# LTC3109.net
KiCad netlist of a schematic drawn in EAGLE
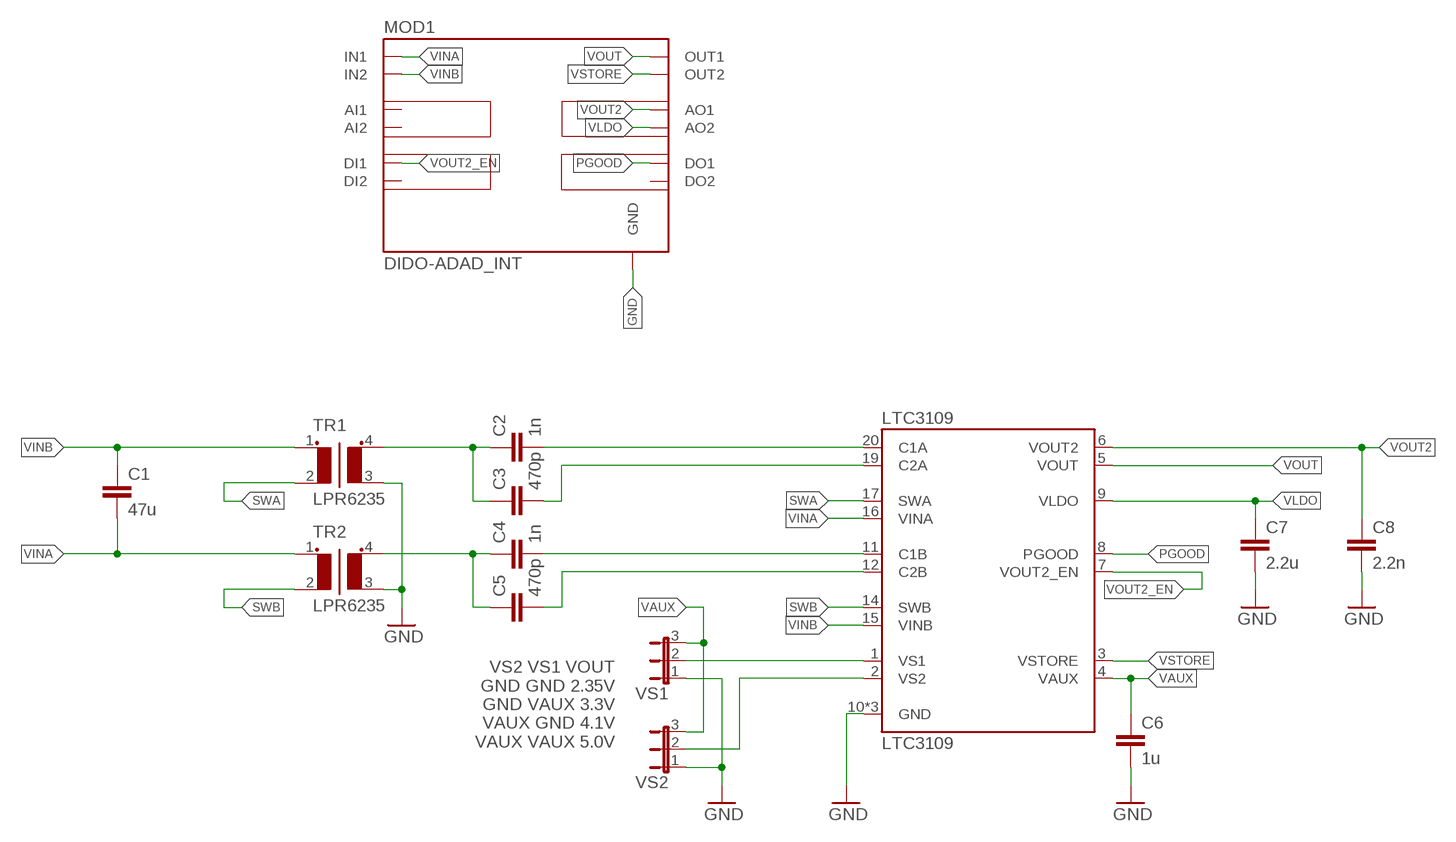
[diagram p0: schematic, sheet 1]

(export (version "E")
  (design (tool "Eeschema 10.0.6"))
  (components
    (comp (ref "C1")
      (value "47u")
      (footprint "eagle-import:C0805")
      (libsource (lib "eagle-import") (part "C-EUC0805"))
    )
    (comp (ref "C2")
      (value "1n")
      (footprint "eagle-import:C0805")
      (libsource (lib "eagle-import") (part "C-EUC0805"))
    )
    (comp (ref "C3")
      (value "470p")
      (footprint "eagle-import:C0805")
      (libsource (lib "eagle-import") (part "C-EUC0805"))
    )
    (comp (ref "C4")
      (value "1n")
      (footprint "eagle-import:C0805")
      (libsource (lib "eagle-import") (part "C-EUC0805"))
    )
    (comp (ref "C5")
      (value "470p")
      (footprint "eagle-import:C0805")
      (libsource (lib "eagle-import") (part "C-EUC0805"))
    )
    (comp (ref "C6")
      (value "1u")
      (footprint "eagle-import:C0805")
      (libsource (lib "eagle-import") (part "C-EUC0805"))
    )
    (comp (ref "C7")
      (value "2.2u")
      (footprint "eagle-import:C0805")
      (libsource (lib "eagle-import") (part "C-EUC0805"))
    )
    (comp (ref "C8")
      (value "2.2n")
      (footprint "eagle-import:C0805")
      (libsource (lib "eagle-import") (part "C-EUC0805"))
    )
    (comp (ref "LTC3109")
      (value "LTC3109")
      (footprint "eagle-import:SSOP20_NARROW")
      (libsource (lib "eagle-import") (part "LTC3109"))
    )
    (comp (ref "MOD1")
      (value "DIDO-ADAD_INT")
      (footprint "eagle-import:DIDO-ADAD")
      (libsource (lib "eagle-import") (part "DIDO-ADAD_INT"))
    )
    (comp (ref "TR1")
      (value "LPR6235")
      (footprint "eagle-import:LPR6235")
      (libsource (lib "eagle-import") (part "LPR6235"))
    )
    (comp (ref "TR2")
      (value "LPR6235")
      (footprint "eagle-import:LPR6235")
      (libsource (lib "eagle-import") (part "LPR6235"))
    )
    (comp (ref "VS1")
      (value "JP2E")
      (footprint "eagle-import:JP2")
      (libsource (lib "eagle-import") (part "JP2E"))
    )
    (comp (ref "VS2")
      (value "JP2E")
      (footprint "eagle-import:JP2")
      (libsource (lib "eagle-import") (part "JP2E"))
    )
  )
  (nets
    (net (code "1") (name "GND") (class "Default")
      (node (ref "C6") (pin "2") (pinfunction "2_2") (pintype "passive"))
      (node (ref "C7") (pin "2") (pinfunction "2_2") (pintype "passive"))
      (node (ref "C8") (pin "2") (pinfunction "2_2") (pintype "passive"))
      (node (ref "LTC3109") (pin "10") (pinfunction "GND_10") (pintype "power_in"))
      (node (ref "LTC3109") (pin "13") (pinfunction "GND_13") (pintype "power_in"))
      (node (ref "LTC3109") (pin "18") (pinfunction "GND_18") (pintype "power_in"))
      (node (ref "MOD1") (pin "GND1") (pinfunction "GND_GND1") (pintype "power_in"))
      (node (ref "MOD1") (pin "GND2") (pinfunction "GND_GND2") (pintype "power_in"))
      (node (ref "MOD1") (pin "GND3") (pinfunction "GND_GND3") (pintype "power_in"))
      (node (ref "MOD1") (pin "GND4") (pinfunction "GND_GND4") (pintype "power_in"))
      (node (ref "TR1") (pin "3") (pinfunction "S2_3") (pintype "passive"))
      (node (ref "TR2") (pin "3") (pinfunction "S2_3") (pintype "passive"))
      (node (ref "VS1") (pin "1") (pinfunction "1_1") (pintype "passive"))
      (node (ref "VS2") (pin "1") (pinfunction "1_1") (pintype "passive"))
    )
    (net (code "2") (name "Net-(LTC3109-C1A)") (class "Default")
      (node (ref "C2") (pin "2") (pinfunction "2_2") (pintype "passive"))
      (node (ref "LTC3109") (pin "20") (pinfunction "C1A_20") (pintype "input"))
    )
    (net (code "3") (name "Net-(LTC3109-C1B)") (class "Default")
      (node (ref "C4") (pin "2") (pinfunction "2_2") (pintype "passive"))
      (node (ref "LTC3109") (pin "11") (pinfunction "C1B_11") (pintype "input"))
    )
    (net (code "4") (name "Net-(LTC3109-C2A)") (class "Default")
      (node (ref "C3") (pin "2") (pinfunction "2_2") (pintype "passive"))
      (node (ref "LTC3109") (pin "19") (pinfunction "C2A_19") (pintype "input"))
    )
    (net (code "5") (name "Net-(LTC3109-C2B)") (class "Default")
      (node (ref "C5") (pin "2") (pinfunction "2_2") (pintype "passive"))
      (node (ref "LTC3109") (pin "12") (pinfunction "C2B_12") (pintype "input"))
    )
    (net (code "6") (name "Net-(LTC3109-VS1)") (class "Default")
      (node (ref "LTC3109") (pin "1") (pinfunction "VS1_1") (pintype "bidirectional"))
      (node (ref "VS1") (pin "2") (pinfunction "2_2") (pintype "passive"))
    )
    (net (code "7") (name "Net-(LTC3109-VS2)") (class "Default")
      (node (ref "LTC3109") (pin "2") (pinfunction "VS2_2") (pintype "bidirectional"))
      (node (ref "VS2") (pin "2") (pinfunction "2_2") (pintype "passive"))
    )
    (net (code "8") (name "Net-(TR1-S1)") (class "Default")
      (node (ref "C2") (pin "1") (pinfunction "1_1") (pintype "passive"))
      (node (ref "C3") (pin "1") (pinfunction "1_1") (pintype "passive"))
      (node (ref "TR1") (pin "4") (pinfunction "S1_4") (pintype "passive"))
    )
    (net (code "9") (name "Net-(TR2-S1)") (class "Default")
      (node (ref "C4") (pin "1") (pinfunction "1_1") (pintype "passive"))
      (node (ref "C5") (pin "1") (pinfunction "1_1") (pintype "passive"))
      (node (ref "TR2") (pin "4") (pinfunction "S1_4") (pintype "passive"))
    )
    (net (code "10") (name "PGOOD") (class "Default")
      (node (ref "LTC3109") (pin "8") (pinfunction "PGOOD_8") (pintype "output"))
      (node (ref "MOD1") (pin "DO1") (pinfunction "DO1_DO1") (pintype "input"))
    )
    (net (code "11") (name "SWA") (class "Default")
      (node (ref "LTC3109") (pin "17") (pinfunction "SWA_17") (pintype "bidirectional"))
      (node (ref "TR1") (pin "2") (pinfunction "P2_2") (pintype "passive"))
    )
    (net (code "12") (name "SWB") (class "Default")
      (node (ref "LTC3109") (pin "14") (pinfunction "SWB_14") (pintype "bidirectional"))
      (node (ref "TR2") (pin "2") (pinfunction "P2_2") (pintype "passive"))
    )
    (net (code "13") (name "VAUX") (class "Default")
      (node (ref "C6") (pin "1") (pinfunction "1_1") (pintype "passive"))
      (node (ref "LTC3109") (pin "4") (pinfunction "VAUX_4") (pintype "output"))
      (node (ref "VS1") (pin "3") (pinfunction "3_3") (pintype "passive"))
      (node (ref "VS2") (pin "3") (pinfunction "3_3") (pintype "passive"))
    )
    (net (code "14") (name "VINA") (class "Default")
      (node (ref "C1") (pin "2") (pinfunction "2_2") (pintype "passive"))
      (node (ref "LTC3109") (pin "16") (pinfunction "VINA_16") (pintype "bidirectional"))
      (node (ref "MOD1") (pin "IN1_1") (pinfunction "IN1_IN1_1") (pintype "output"))
      (node (ref "MOD1") (pin "IN1_2") (pinfunction "IN1_IN1_2") (pintype "output"))
      (node (ref "MOD1") (pin "IN1_3") (pinfunction "IN1_IN1_3") (pintype "output"))
      (node (ref "MOD1") (pin "IN1_4") (pinfunction "IN1_IN1_4") (pintype "output"))
      (node (ref "TR2") (pin "1") (pinfunction "P1_1") (pintype "passive"))
    )
    (net (code "15") (name "VINB") (class "Default")
      (node (ref "C1") (pin "1") (pinfunction "1_1") (pintype "passive"))
      (node (ref "LTC3109") (pin "15") (pinfunction "VINB_15") (pintype "bidirectional"))
      (node (ref "MOD1") (pin "IN2_1") (pinfunction "IN2_IN2_1") (pintype "output"))
      (node (ref "MOD1") (pin "IN2_2") (pinfunction "IN2_IN2_2") (pintype "output"))
      (node (ref "MOD1") (pin "IN2_3") (pinfunction "IN2_IN2_3") (pintype "output"))
      (node (ref "MOD1") (pin "IN2_4") (pinfunction "IN2_IN2_4") (pintype "output"))
      (node (ref "TR1") (pin "1") (pinfunction "P1_1") (pintype "passive"))
    )
    (net (code "16") (name "VLDO") (class "Default")
      (node (ref "C7") (pin "1") (pinfunction "1_1") (pintype "passive"))
      (node (ref "LTC3109") (pin "9") (pinfunction "VLDO_9") (pintype "output"))
      (node (ref "MOD1") (pin "AO2") (pinfunction "AO2_AO2") (pintype "input"))
    )
    (net (code "17") (name "VOUT") (class "Default")
      (node (ref "LTC3109") (pin "5") (pinfunction "VOUT_5") (pintype "output"))
      (node (ref "MOD1") (pin "OUT1_1") (pinfunction "OUT1_OUT1_1") (pintype "input"))
      (node (ref "MOD1") (pin "OUT1_2") (pinfunction "OUT1_OUT1_2") (pintype "input"))
      (node (ref "MOD1") (pin "OUT1_3") (pinfunction "OUT1_OUT1_3") (pintype "input"))
      (node (ref "MOD1") (pin "OUT1_4") (pinfunction "OUT1_OUT1_4") (pintype "input"))
    )
    (net (code "18") (name "VOUT2") (class "Default")
      (node (ref "C8") (pin "1") (pinfunction "1_1") (pintype "passive"))
      (node (ref "LTC3109") (pin "6") (pinfunction "VOUT2_6") (pintype "output"))
      (node (ref "MOD1") (pin "AO1") (pinfunction "AO1_AO1") (pintype "input"))
    )
    (net (code "19") (name "VOUT2_EN") (class "Default")
      (node (ref "LTC3109") (pin "7") (pinfunction "VOUT2_EN_7") (pintype "input"))
      (node (ref "MOD1") (pin "DI1") (pinfunction "DI1_DI1") (pintype "output"))
    )
    (net (code "20") (name "VSTORE") (class "Default")
      (node (ref "LTC3109") (pin "3") (pinfunction "VSTORE_3") (pintype "output"))
      (node (ref "MOD1") (pin "OUT2_1") (pinfunction "OUT2_OUT2_1") (pintype "input"))
      (node (ref "MOD1") (pin "OUT2_2") (pinfunction "OUT2_OUT2_2") (pintype "input"))
      (node (ref "MOD1") (pin "OUT2_3") (pinfunction "OUT2_OUT2_3") (pintype "input"))
      (node (ref "MOD1") (pin "OUT2_4") (pinfunction "OUT2_OUT2_4") (pintype "input"))
    )
    (net (code "21") (name "unconnected-(MOD1-PadAI1)") (class "Default")
      (node (ref "MOD1") (pin "AI1") (pinfunction "AI1_AI1") (pintype "output"))
    )
    (net (code "22") (name "unconnected-(MOD1-PadAI2)") (class "Default")
      (node (ref "MOD1") (pin "AI2") (pinfunction "AI2_AI2") (pintype "output"))
    )
    (net (code "23") (name "unconnected-(MOD1-PadDI2)") (class "Default")
      (node (ref "MOD1") (pin "DI2") (pinfunction "DI2_DI2") (pintype "output"))
    )
    (net (code "24") (name "unconnected-(MOD1-PadDO2)") (class "Default")
      (node (ref "MOD1") (pin "DO2") (pinfunction "DO2_DO2") (pintype "input"))
    )
  )
)
